# Ctrl_Enc20.net
KiCad netlist of a schematic drawn in EAGLE
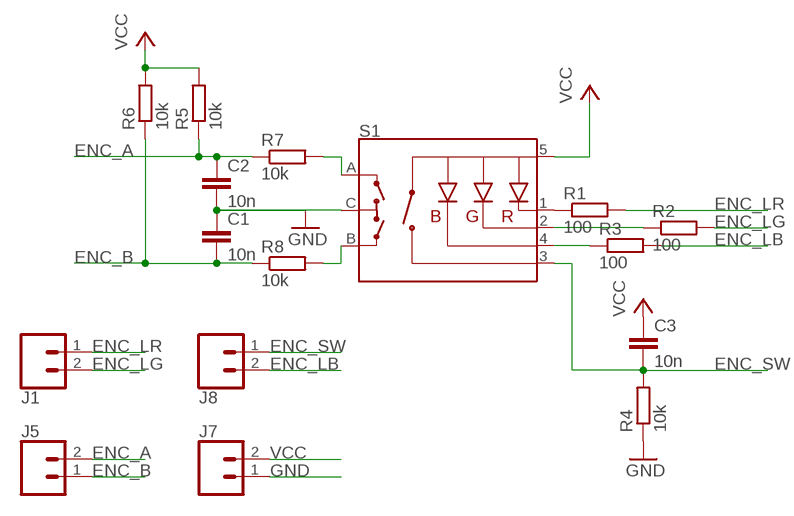
[diagram p0: schematic, sheet 1]

(export (version "E")
  (design (tool "Eeschema 10.0.6"))
  (components
    (comp (ref "C1")
      (value "10n")
      (footprint "eagle-import:C0603")
      (libsource (lib "eagle-import") (part "C-EUC0603"))
    )
    (comp (ref "C2")
      (value "10n")
      (footprint "eagle-import:C0603")
      (libsource (lib "eagle-import") (part "C-EUC0603"))
    )
    (comp (ref "C3")
      (value "10n")
      (footprint "eagle-import:C0603")
      (libsource (lib "eagle-import") (part "C-EUC0603"))
    )
    (comp (ref "J1")
      (value "CONN_02")
      (footprint "eagle-import:1X02")
      (libsource (lib "eagle-import") (part "CONN_02"))
    )
    (comp (ref "J5")
      (value "CONN_02")
      (footprint "eagle-import:1X02")
      (libsource (lib "eagle-import") (part "CONN_02"))
    )
    (comp (ref "J7")
      (value "CONN_02")
      (footprint "eagle-import:1X02")
      (libsource (lib "eagle-import") (part "CONN_02"))
    )
    (comp (ref "J8")
      (value "CONN_02")
      (footprint "eagle-import:1X02")
      (libsource (lib "eagle-import") (part "CONN_02"))
    )
    (comp (ref "R1")
      (value "100")
      (footprint "eagle-import:R0603")
      (libsource (lib "eagle-import") (part "R-EU_R0603"))
    )
    (comp (ref "R2")
      (value "100")
      (footprint "eagle-import:R0603")
      (libsource (lib "eagle-import") (part "R-EU_R0603"))
    )
    (comp (ref "R3")
      (value "100")
      (footprint "eagle-import:R0603")
      (libsource (lib "eagle-import") (part "R-EU_R0603"))
    )
    (comp (ref "R4")
      (value "10k")
      (footprint "eagle-import:R0603")
      (libsource (lib "eagle-import") (part "R-EU_R0603"))
    )
    (comp (ref "R5")
      (value "10k")
      (footprint "eagle-import:R0603")
      (libsource (lib "eagle-import") (part "R-EU_R0603"))
    )
    (comp (ref "R6")
      (value "10k")
      (footprint "eagle-import:R0603")
      (libsource (lib "eagle-import") (part "R-EU_R0603"))
    )
    (comp (ref "R7")
      (value "10k")
      (footprint "eagle-import:R0603")
      (libsource (lib "eagle-import") (part "R-EU_R0603"))
    )
    (comp (ref "R8")
      (value "10k")
      (footprint "eagle-import:R0603")
      (libsource (lib "eagle-import") (part "R-EU_R0603"))
    )
    (comp (ref "S1")
      (value "ENCODER-RGB-SWITCH")
      (footprint "eagle-import:ENCODER_LED_3")
      (libsource (lib "eagle-import") (part "ENCODER-RGB-SWITCH"))
    )
  )
  (nets
    (net (code "1") (name "/ENC_A") (class "Default")
      (node (ref "C2") (pin "1") (pinfunction "1_1") (pintype "passive"))
      (node (ref "J5") (pin "2") (pinfunction "2_2") (pintype "passive"))
      (node (ref "R5") (pin "1") (pinfunction "1_1") (pintype "passive"))
      (node (ref "R7") (pin "1") (pinfunction "1_1") (pintype "passive"))
    )
    (net (code "2") (name "/ENC_B") (class "Default")
      (node (ref "C1") (pin "2") (pinfunction "2_2") (pintype "passive"))
      (node (ref "J5") (pin "1") (pinfunction "1_1") (pintype "passive"))
      (node (ref "R6") (pin "1") (pinfunction "1_1") (pintype "passive"))
      (node (ref "R8") (pin "1") (pinfunction "1_1") (pintype "passive"))
    )
    (net (code "3") (name "/ENC_LB") (class "Default")
      (node (ref "J8") (pin "2") (pinfunction "2_2") (pintype "passive"))
      (node (ref "R3") (pin "2") (pinfunction "2_2") (pintype "passive"))
    )
    (net (code "4") (name "/ENC_LG") (class "Default")
      (node (ref "J1") (pin "2") (pinfunction "2_2") (pintype "passive"))
      (node (ref "R2") (pin "2") (pinfunction "2_2") (pintype "passive"))
    )
    (net (code "5") (name "/ENC_LR") (class "Default")
      (node (ref "J1") (pin "1") (pinfunction "1_1") (pintype "passive"))
      (node (ref "R1") (pin "2") (pinfunction "2_2") (pintype "passive"))
    )
    (net (code "6") (name "/ENC_SW") (class "Default")
      (node (ref "C3") (pin "2") (pinfunction "2_2") (pintype "passive"))
      (node (ref "J8") (pin "1") (pinfunction "1_1") (pintype "passive"))
      (node (ref "R4") (pin "2") (pinfunction "2_2") (pintype "passive"))
      (node (ref "S1") (pin "3") (pinfunction "SW_3") (pintype "passive"))
    )
    (net (code "7") (name "GND") (class "Default")
      (node (ref "C1") (pin "1") (pinfunction "1_1") (pintype "passive"))
      (node (ref "C2") (pin "2") (pinfunction "2_2") (pintype "passive"))
      (node (ref "J7") (pin "1") (pinfunction "1_1") (pintype "passive"))
      (node (ref "R4") (pin "1") (pinfunction "1_1") (pintype "passive"))
      (node (ref "S1") (pin "C") (pinfunction "C_C") (pintype "bidirectional"))
    )
    (net (code "8") (name "Net-(R7-Pad2)") (class "Default")
      (node (ref "R7") (pin "2") (pinfunction "2_2") (pintype "passive"))
      (node (ref "S1") (pin "A") (pinfunction "A_A") (pintype "bidirectional"))
    )
    (net (code "9") (name "Net-(R8-Pad2)") (class "Default")
      (node (ref "R8") (pin "2") (pinfunction "2_2") (pintype "passive"))
      (node (ref "S1") (pin "B") (pinfunction "B_B") (pintype "bidirectional"))
    )
    (net (code "10") (name "Net-(S1--B)") (class "Default")
      (node (ref "R3") (pin "1") (pinfunction "1_1") (pintype "passive"))
      (node (ref "S1") (pin "4") (pinfunction "-B_4") (pintype "passive"))
    )
    (net (code "11") (name "Net-(S1--G)") (class "Default")
      (node (ref "R2") (pin "1") (pinfunction "1_1") (pintype "passive"))
      (node (ref "S1") (pin "2") (pinfunction "-G_2") (pintype "passive"))
    )
    (net (code "12") (name "Net-(S1--R)") (class "Default")
      (node (ref "R1") (pin "1") (pinfunction "1_1") (pintype "passive"))
      (node (ref "S1") (pin "1") (pinfunction "-R_1") (pintype "passive"))
    )
    (net (code "13") (name "VCC") (class "Default")
      (node (ref "C3") (pin "1") (pinfunction "1_1") (pintype "passive"))
      (node (ref "J7") (pin "2") (pinfunction "2_2") (pintype "passive"))
      (node (ref "R5") (pin "2") (pinfunction "2_2") (pintype "passive"))
      (node (ref "R6") (pin "2") (pinfunction "2_2") (pintype "passive"))
      (node (ref "S1") (pin "5") (pinfunction "+_5") (pintype "passive"))
    )
  )
)
